# Isengard.net
KiCad netlist of a schematic drawn in Altium Designer
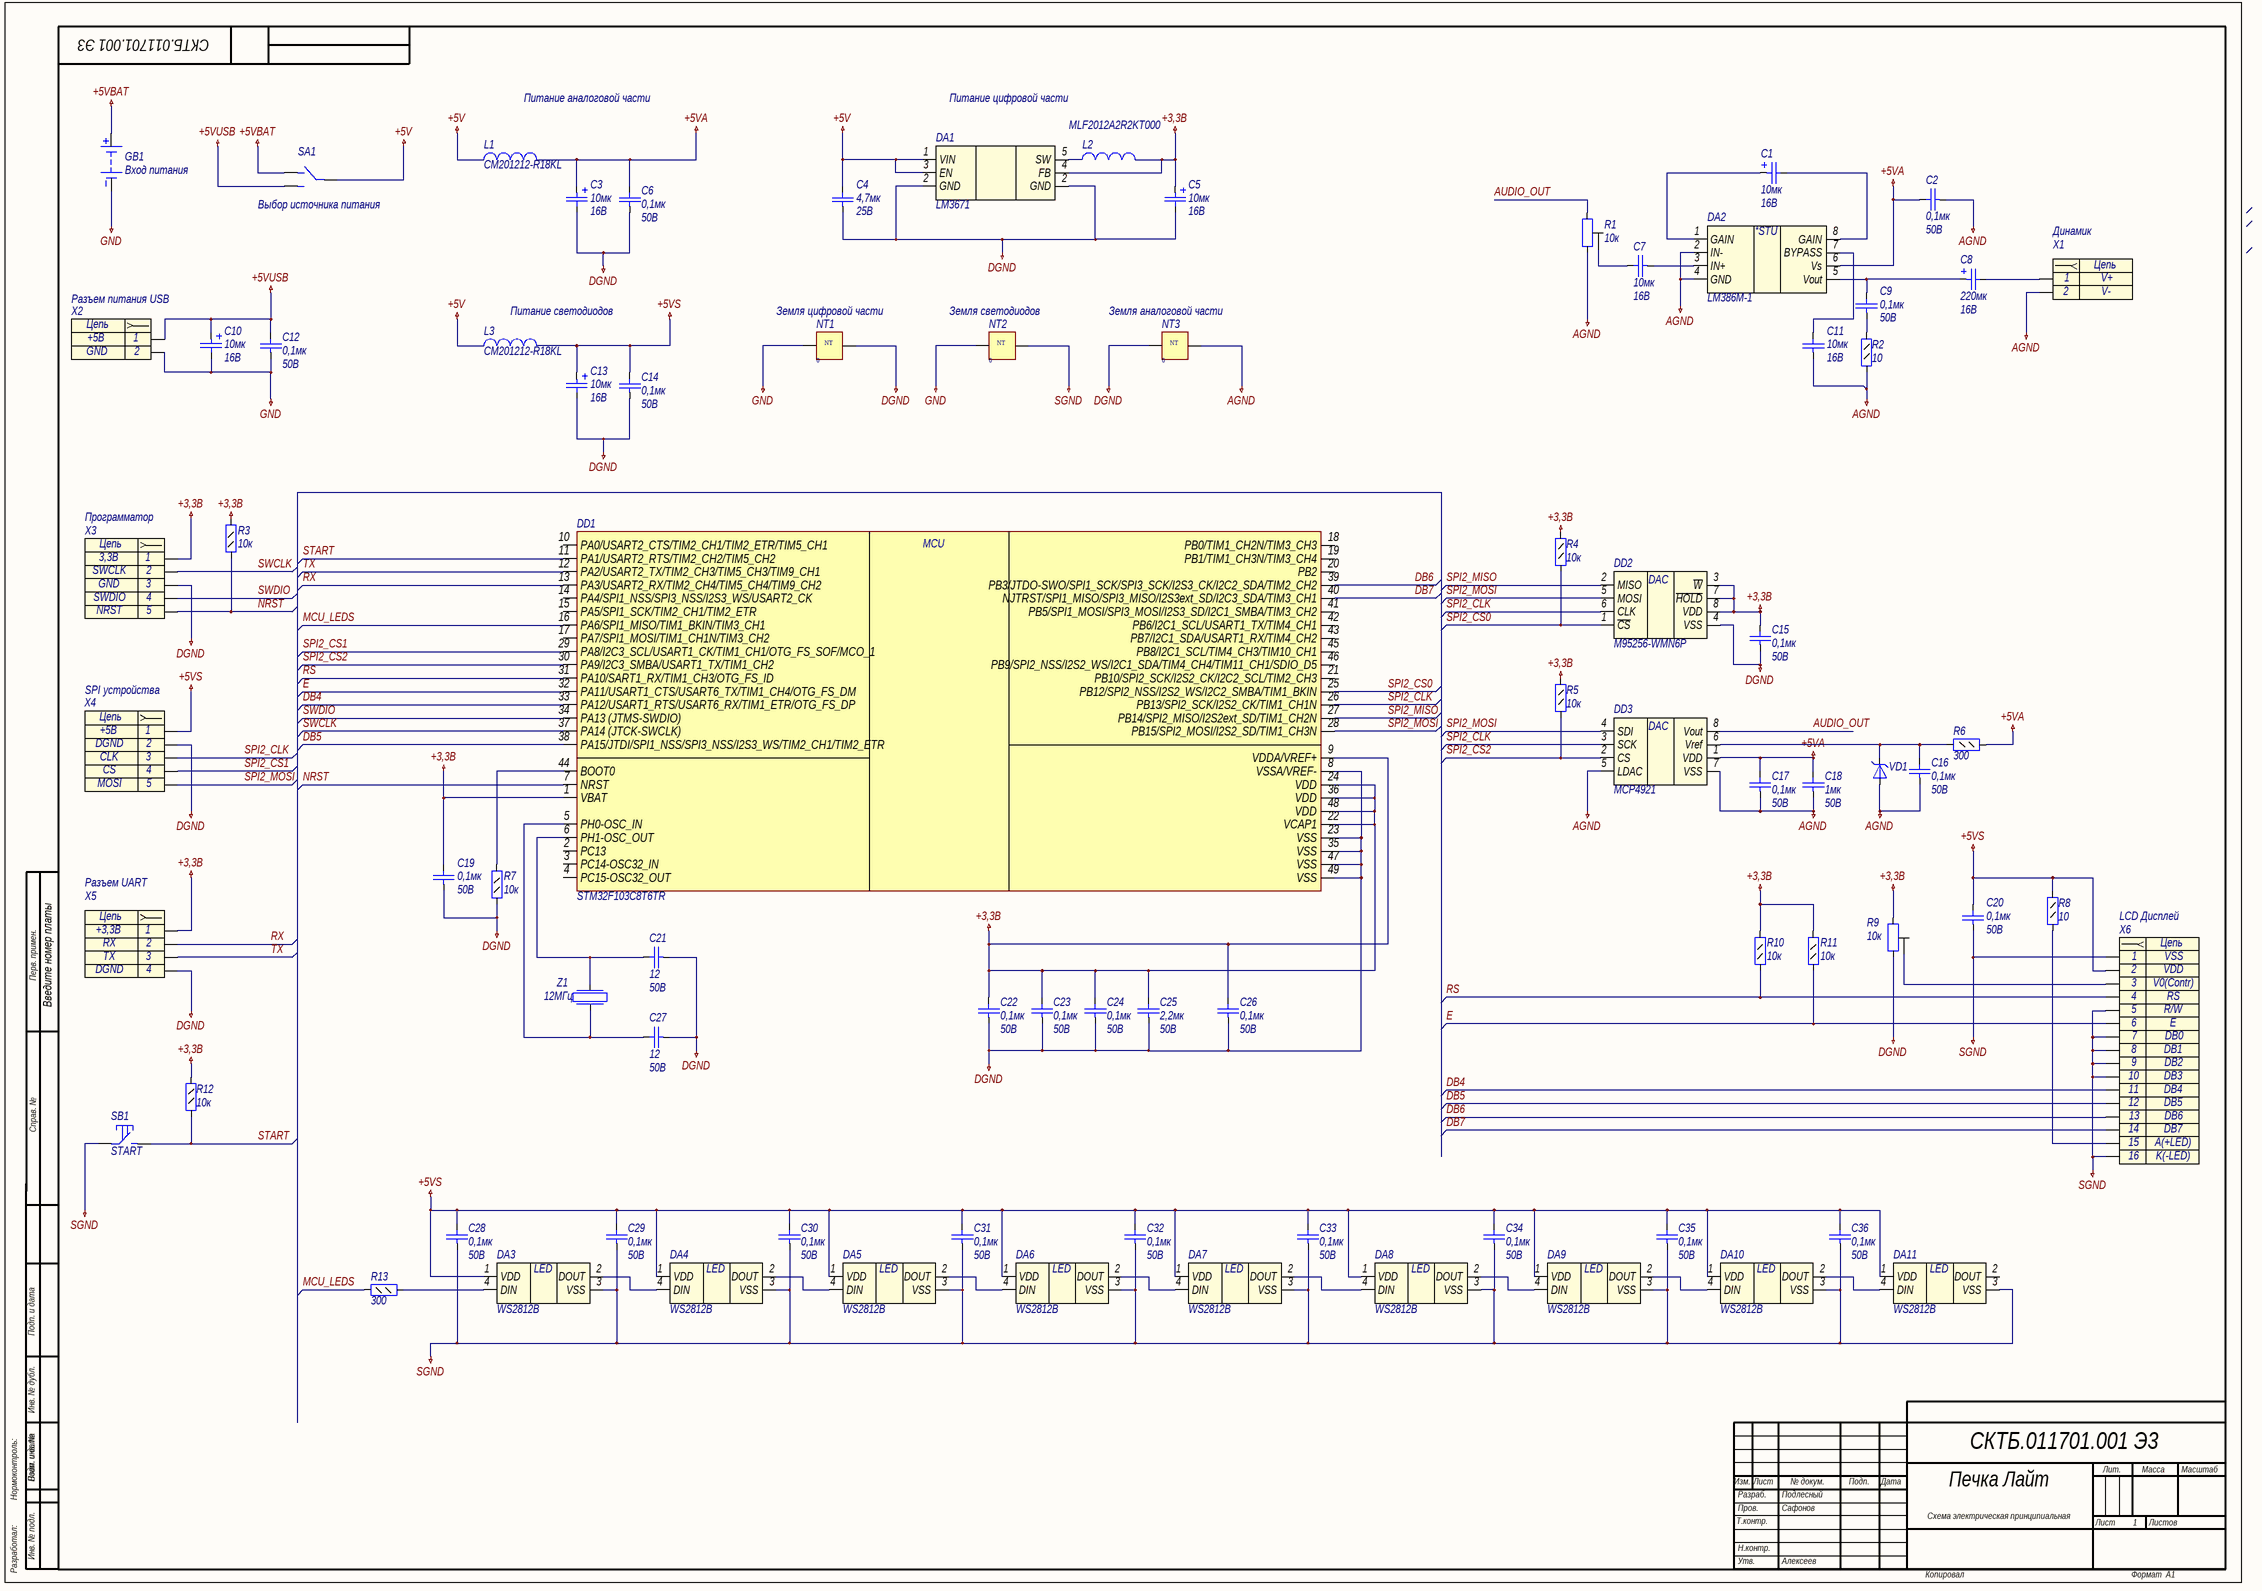
[diagram p0: Isengard.SchDoc]

(export (version "E")
  (design (tool "Eeschema 10.0.6"))
  (components
    (comp (ref "C1")
      (value "10мк")
      (footprint "ZabugorLib:TANTAL CASE B")
      (description "Конденсатор полярный")
      (fields (field (name "VOLTAGE") "16В"))
      (libsource (lib "Isengard") (part "Capacitor_pol"))
    )
    (comp (ref "C2")
      (value "0,1мк")
      (footprint "Isengard:C0805")
      (description "Конденсатор")
      (fields (field (name "VOLTAGE") "50В"))
      (libsource (lib "Isengard") (part "Capacitor"))
    )
    (comp (ref "C3")
      (value "10мк")
      (footprint "ZabugorLib:TANTAL CASE B")
      (description "Конденсатор полярный")
      (fields (field (name "VOLTAGE") "16В"))
      (libsource (lib "Isengard") (part "Capacitor_pol"))
    )
    (comp (ref "C4")
      (value "4,7мк")
      (footprint "ZabugorLib:C0805")
      (description "Конденсатор")
      (fields (field (name "VOLTAGE") "25В"))
      (libsource (lib "Isengard") (part "Capacitor"))
    )
    (comp (ref "C5")
      (value "10мк")
      (footprint "ZabugorLib:TANTAL CASE B")
      (description "Конденсатор полярный")
      (fields (field (name "VOLTAGE") "16В"))
      (libsource (lib "Isengard") (part "Capacitor_pol"))
    )
    (comp (ref "C6")
      (value "0,1мк")
      (footprint "ZabugorLib:C0805")
      (description "Конденсатор")
      (fields (field (name "VOLTAGE") "50В"))
      (libsource (lib "Isengard") (part "Capacitor"))
    )
    (comp (ref "C7")
      (value "10мк")
      (footprint "Isengard:C0805")
      (description "Конденсатор")
      (fields (field (name "VOLTAGE") "16В"))
      (libsource (lib "Isengard") (part "Capacitor"))
    )
    (comp (ref "C8")
      (value "220мк")
      (footprint "Isengard:TANTAL CASE D")
      (description "Конденсатор полярный")
      (fields (field (name "VOLTAGE") "16В"))
      (libsource (lib "Isengard") (part "Capacitor_pol"))
    )
    (comp (ref "C9")
      (value "0,1мк")
      (footprint "Isengard:C0805")
      (description "Конденсатор")
      (fields (field (name "VOLTAGE") "50В"))
      (libsource (lib "Isengard") (part "Capacitor"))
    )
    (comp (ref "C10")
      (value "10мк")
      (footprint "ZabugorLib:TANTAL CASE B")
      (description "Конденсатор полярный")
      (fields (field (name "VOLTAGE") "16В"))
      (libsource (lib "Isengard") (part "Capacitor_pol"))
    )
    (comp (ref "C11")
      (value "10мк")
      (footprint "Isengard:C0805")
      (description "Конденсатор")
      (fields (field (name "VOLTAGE") "16В"))
      (libsource (lib "Isengard") (part "Capacitor"))
    )
    (comp (ref "C12")
      (value "0,1мк")
      (footprint "ZabugorLib:C0805")
      (description "Конденсатор")
      (fields (field (name "VOLTAGE") "50В"))
      (libsource (lib "Isengard") (part "Capacitor"))
    )
    (comp (ref "C13")
      (value "10мк")
      (footprint "ZabugorLib:TANTAL CASE B")
      (description "Конденсатор полярный")
      (fields (field (name "VOLTAGE") "16В"))
      (libsource (lib "Isengard") (part "Capacitor_pol"))
    )
    (comp (ref "C14")
      (value "0,1мк")
      (footprint "ZabugorLib:C0805")
      (description "Конденсатор")
      (fields (field (name "VOLTAGE") "50В"))
      (libsource (lib "Isengard") (part "Capacitor"))
    )
    (comp (ref "C15")
      (value "0,1мк")
      (footprint "ZabugorLib:C0805")
      (description "Конденсатор")
      (fields (field (name "VOLTAGE") "50В"))
      (libsource (lib "Isengard") (part "Capacitor"))
    )
    (comp (ref "C16")
      (value "0,1мк")
      (footprint "ZabugorLib:C0805")
      (description "Конденсатор")
      (fields (field (name "VOLTAGE") "50В"))
      (libsource (lib "Isengard") (part "Capacitor"))
    )
    (comp (ref "C17")
      (value "0,1мк")
      (footprint "ZabugorLib:C0805")
      (description "Конденсатор")
      (fields (field (name "VOLTAGE") "50В"))
      (libsource (lib "Isengard") (part "Capacitor"))
    )
    (comp (ref "C18")
      (value "1мк")
      (footprint "ZabugorLib:C0805")
      (description "Конденсатор")
      (fields (field (name "VOLTAGE") "50В"))
      (libsource (lib "Isengard") (part "Capacitor"))
    )
    (comp (ref "C19")
      (value "0,1мк")
      (footprint "ZabugorLib:C0805")
      (description "Конденсатор")
      (fields (field (name "VOLTAGE") "50В"))
      (libsource (lib "Isengard") (part "Capacitor"))
    )
    (comp (ref "C20")
      (value "0,1мк")
      (footprint "Isengard:C0805")
      (description "Конденсатор")
      (fields (field (name "VOLTAGE") "50В"))
      (libsource (lib "Isengard") (part "Capacitor"))
    )
    (comp (ref "C21")
      (value "12")
      (footprint "ZabugorLib:C0805")
      (description "Конденсатор")
      (fields (field (name "VOLTAGE") "50В"))
      (libsource (lib "Isengard") (part "Capacitor"))
    )
    (comp (ref "C22")
      (value "0,1мк")
      (footprint "ZabugorLib:C0805")
      (description "Конденсатор")
      (fields (field (name "VOLTAGE") "50В"))
      (libsource (lib "Isengard") (part "Capacitor"))
    )
    (comp (ref "C23")
      (value "0,1мк")
      (footprint "ZabugorLib:C0805")
      (description "Конденсатор")
      (fields (field (name "VOLTAGE") "50В"))
      (libsource (lib "Isengard") (part "Capacitor"))
    )
    (comp (ref "C24")
      (value "0,1мк")
      (footprint "ZabugorLib:C0805")
      (description "Конденсатор")
      (fields (field (name "VOLTAGE") "50В"))
      (libsource (lib "Isengard") (part "Capacitor"))
    )
    (comp (ref "C25")
      (value "2,2мк")
      (footprint "ZabugorLib:C0805")
      (description "Конденсатор")
      (fields (field (name "VOLTAGE") "50В"))
      (libsource (lib "Isengard") (part "Capacitor"))
    )
    (comp (ref "C26")
      (value "0,1мк")
      (footprint "ZabugorLib:C0805")
      (description "Конденсатор")
      (fields (field (name "VOLTAGE") "50В"))
      (libsource (lib "Isengard") (part "Capacitor"))
    )
    (comp (ref "C27")
      (value "12")
      (footprint "ZabugorLib:C0805")
      (description "Конденсатор")
      (fields (field (name "VOLTAGE") "50В"))
      (libsource (lib "Isengard") (part "Capacitor"))
    )
    (comp (ref "C28")
      (value "0,1мк")
      (footprint "ZabugorLib:C0805")
      (description "Конденсатор")
      (fields (field (name "VOLTAGE") "50В"))
      (libsource (lib "Isengard") (part "Capacitor"))
    )
    (comp (ref "C29")
      (value "0,1мк")
      (footprint "ZabugorLib:C0805")
      (description "Конденсатор")
      (fields (field (name "VOLTAGE") "50В"))
      (libsource (lib "Isengard") (part "Capacitor"))
    )
    (comp (ref "C30")
      (value "0,1мк")
      (footprint "ZabugorLib:C0805")
      (description "Конденсатор")
      (fields (field (name "VOLTAGE") "50В"))
      (libsource (lib "Isengard") (part "Capacitor"))
    )
    (comp (ref "C31")
      (value "0,1мк")
      (footprint "ZabugorLib:C0805")
      (description "Конденсатор")
      (fields (field (name "VOLTAGE") "50В"))
      (libsource (lib "Isengard") (part "Capacitor"))
    )
    (comp (ref "C32")
      (value "0,1мк")
      (footprint "ZabugorLib:C0805")
      (description "Конденсатор")
      (fields (field (name "VOLTAGE") "50В"))
      (libsource (lib "Isengard") (part "Capacitor"))
    )
    (comp (ref "C33")
      (value "0,1мк")
      (footprint "ZabugorLib:C0805")
      (description "Конденсатор")
      (fields (field (name "VOLTAGE") "50В"))
      (libsource (lib "Isengard") (part "Capacitor"))
    )
    (comp (ref "C34")
      (value "0,1мк")
      (footprint "ZabugorLib:C0805")
      (description "Конденсатор")
      (fields (field (name "VOLTAGE") "50В"))
      (libsource (lib "Isengard") (part "Capacitor"))
    )
    (comp (ref "C35")
      (value "0,1мк")
      (footprint "ZabugorLib:C0805")
      (description "Конденсатор")
      (fields (field (name "VOLTAGE") "50В"))
      (libsource (lib "Isengard") (part "Capacitor"))
    )
    (comp (ref "C36")
      (value "0,1мк")
      (footprint "ZabugorLib:C0805")
      (description "Конденсатор")
      (fields (field (name "VOLTAGE") "50В"))
      (libsource (lib "Isengard") (part "Capacitor"))
    )
    (comp (ref "DA1")
      (value "LM3671")
      (footprint "ZabugorLib:SOT23-5")
      (description "600-mA Step-Down DC-DC Converter")
      (libsource (lib "ZabugorLib") (part "LM3671"))
    )
    (comp (ref "DA2")
      (value "LM386M-1")
      (footprint "ZabugorLib:SO8")
      (description "Low Voltage Audio Power Amplifier")
      (libsource (lib "Isengard") (part "LM386M-1"))
    )
    (comp (ref "DA3")
      (value "WS2812B")
      (footprint "Isengard:WS2812B")
      (description "Светодиод SMD RGB с пиксельной адресацией")
      (fields (field (name "NAME") "WS2812B"))
      (libsource (lib "Isengard") (part "WS2812B"))
    )
    (comp (ref "DA4")
      (value "WS2812B")
      (footprint "Isengard:WS2812B")
      (description "Светодиод SMD RGB с пиксельной адресацией")
      (fields (field (name "NAME") "WS2812B"))
      (libsource (lib "Isengard") (part "WS2812B"))
    )
    (comp (ref "DA5")
      (value "WS2812B")
      (footprint "Isengard:WS2812B")
      (description "Светодиод SMD RGB с пиксельной адресацией")
      (fields (field (name "NAME") "WS2812B"))
      (libsource (lib "Isengard") (part "WS2812B"))
    )
    (comp (ref "DA6")
      (value "WS2812B")
      (footprint "Isengard:WS2812B")
      (description "Светодиод SMD RGB с пиксельной адресацией")
      (fields (field (name "NAME") "WS2812B"))
      (libsource (lib "Isengard") (part "WS2812B"))
    )
    (comp (ref "DA7")
      (value "WS2812B")
      (footprint "Isengard:WS2812B")
      (description "Светодиод SMD RGB с пиксельной адресацией")
      (fields (field (name "NAME") "WS2812B"))
      (libsource (lib "Isengard") (part "WS2812B"))
    )
    (comp (ref "DA8")
      (value "WS2812B")
      (footprint "Isengard:WS2812B")
      (description "Светодиод SMD RGB с пиксельной адресацией")
      (fields (field (name "NAME") "WS2812B"))
      (libsource (lib "Isengard") (part "WS2812B"))
    )
    (comp (ref "DA9")
      (value "WS2812B")
      (footprint "Isengard:WS2812B")
      (description "Светодиод SMD RGB с пиксельной адресацией")
      (fields (field (name "NAME") "WS2812B"))
      (libsource (lib "Isengard") (part "WS2812B"))
    )
    (comp (ref "DA10")
      (value "WS2812B")
      (footprint "Isengard:WS2812B")
      (description "Светодиод SMD RGB с пиксельной адресацией")
      (fields (field (name "NAME") "WS2812B"))
      (libsource (lib "Isengard") (part "WS2812B"))
    )
    (comp (ref "DA11")
      (value "WS2812B")
      (footprint "Isengard:WS2812B")
      (description "Светодиод SMD RGB с пиксельной адресацией")
      (fields (field (name "NAME") "WS2812B"))
      (libsource (lib "Isengard") (part "WS2812B"))
    )
    (comp (ref "DD1")
      (value "STM32F103C8T6TR")
      (footprint "ZabugorLib:LQFP48")
      (libsource (lib "ZabugorLib") (part "STM32F103C8T6TR"))
    )
    (comp (ref "DD2")
      (value "M95256-WMN6P")
      (footprint "ZabugorLib:SO8")
      (description "12-Bit DAC with SPI™ Interface")
      (libsource (lib "ZabugorLib") (part "M95256"))
    )
    (comp (ref "DD3")
      (value "MCP4921")
      (footprint "ZabugorLib:SO8")
      (description "12-Bit DAC with SPI™ Interface")
      (libsource (lib "ZabugorLib") (part "MCP4921"))
    )
    (comp (ref "GB1")
      (value "Вход питания")
      (footprint "Isengard:KLS5-818-С")
      (libsource (lib "Isengard") (part "Battery compartment"))
    )
    (comp (ref "L1")
      (value "CM201212-R18KL")
      (footprint "ZabugorLib:L0805")
      (description "Катушка индуктивности")
      (libsource (lib "Isengard") (part "Inductor"))
    )
    (comp (ref "L2")
      (value "MLF2012A2R2KT000")
      (footprint "ZabugorLib:L0805")
      (description "Катушка индуктивности")
      (libsource (lib "Isengard") (part "Inductor"))
    )
    (comp (ref "L3")
      (value "CM201212-R18KL")
      (footprint "ZabugorLib:L0805")
      (description "Катушка индуктивности")
      (libsource (lib "Isengard") (part "Inductor"))
    )
    (comp (ref "NT1")
      (value "0")
      (footprint "Pofigistor0603")
      (fields (field (name "Comment") "Pofigistor"))
      (libsource (lib "MOP44") (part "Pofigistor"))
    )
    (comp (ref "NT2")
      (value "0")
      (footprint "Pofigistor0603")
      (fields (field (name "Comment") "Pofigistor"))
      (libsource (lib "MOP44") (part "Pofigistor"))
    )
    (comp (ref "NT3")
      (value "0")
      (footprint "Pofigistor0603")
      (fields (field (name "Comment") "Pofigistor"))
      (libsource (lib "MOP44") (part "Pofigistor"))
    )
    (comp (ref "R1")
      (value "10к")
      (footprint "ZabugorLib:Potentiometer")
      (description "Potentiometer")
      (libsource (lib "ZabugorLib") (part "Potentiometer"))
    )
    (comp (ref "R2")
      (value "10")
      (footprint "Isengard:R0805")
      (description "Резистор")
      (libsource (lib "") (part "Resistor_0,125Вт_2"))
    )
    (comp (ref "R3")
      (value "10к")
      (footprint "ZabugorLib:R0805")
      (description "Резистор")
      (libsource (lib "Isengard") (part "Resistor_0,125Вт"))
    )
    (comp (ref "R4")
      (value "10к")
      (footprint "ZabugorLib:R0805")
      (description "Резистор")
      (libsource (lib "") (part "Resistor_0,125Вт_2"))
    )
    (comp (ref "R5")
      (value "10к")
      (footprint "ZabugorLib:R0805")
      (description "Резистор")
      (libsource (lib "") (part "Resistor_0,125Вт_2"))
    )
    (comp (ref "R6")
      (value "300")
      (footprint "Isengard:R0805")
      (description "Резистор")
      (libsource (lib "") (part "Resistor_0,125Вт_1"))
    )
    (comp (ref "R7")
      (value "10к")
      (footprint "ZabugorLib:R0805")
      (description "Резистор")
      (libsource (lib "Isengard") (part "Resistor_0,125Вт"))
    )
    (comp (ref "R8")
      (value "10")
      (footprint "Isengard:R0805")
      (description "Резистор")
      (libsource (lib "") (part "Resistor_0,125Вт_2"))
    )
    (comp (ref "R9")
      (value "10к")
      (footprint "ZabugorLib:Potentiometer")
      (description "Potentiometer")
      (libsource (lib "ZabugorLib") (part "Potentiometer"))
    )
    (comp (ref "R10")
      (value "10к")
      (footprint "Isengard:R0805")
      (description "Резистор")
      (libsource (lib "Isengard") (part "Resistor_0,125Вт"))
    )
    (comp (ref "R11")
      (value "10к")
      (footprint "Isengard:R0805")
      (description "Резистор")
      (libsource (lib "Isengard") (part "Resistor_0,125Вт"))
    )
    (comp (ref "R12")
      (value "10к")
      (footprint "Isengard:R0805")
      (description "Резистор")
      (libsource (lib "") (part "Resistor_0,125Вт_2"))
    )
    (comp (ref "R13")
      (value "300")
      (footprint "ZabugorLib:R0805")
      (description "Резистор")
      (libsource (lib "") (part "Resistor_0,125Вт_3"))
    )
    (comp (ref "SA1")
      (value "Выбор источника питания")
      (footprint "Isengard:KLS7-SS03")
      (description "переключатель однопозиционный")
      (fields (field (name "NAME") "Выбор источника питания"))
      (libsource (lib "Isengard") (part "Toggle switch"))
    )
    (comp (ref "SB1")
      (value "START")
      (footprint "Isengard:Button_SMD_12х12")
      (description "Кнопка")
      (fields (field (name "NAME") "START"))
      (libsource (lib "Isengard") (part "Button_SMD"))
    )
    (comp (ref "VD1")
      (value "LM4040BIM3-2.5/NOPB")
      (footprint "SOT23-3")
      (description "Прецезионный источник опорного напряжения")
      (libsource (lib "MOP44") (part "LM4040BIM3-2.5/NOPB"))
    )
    (comp (ref "X1")
      (value "Динамик")
      (footprint "Isengard:DYNAMIC")
      (description "Разъем - 2 конт. розетка")
      (libsource (lib "") (part "Header_2_sct_1"))
    )
    (comp (ref "X2")
      (value "Разъем питания USB")
      (footprint "Isengard:USB-B Micro 2pin")
      (description "Разъем - 2 конт. розетка")
      (libsource (lib "Isengard") (part "Header_2_sct"))
    )
    (comp (ref "X3")
      (value "Программатор")
      (footprint "Isengard:PLS-5")
      (description "Разъем - 4 конт. розетка")
      (libsource (lib "ZabugorLib") (part "Header_5_sct"))
    )
    (comp (ref "X4")
      (value "SPI устройства")
      (footprint "Isengard:5HOLE_WIRE")
      (description "Разъем - 4 конт. розетка")
      (libsource (lib "Isengard") (part "Header_5_sct"))
    )
    (comp (ref "X5")
      (value "Разъем UART")
      (footprint "Isengard:PLS-4")
      (description "Разъем - 4 конт. розетка")
      (libsource (lib "Isengard") (part "Header_4_sct"))
    )
    (comp (ref "X6")
      (value "LCD Дисплей")
      (footprint "Isengard:PLS-16R")
      (description "Разъем - 16 конт. розетка")
      (libsource (lib "Isengard") (part "Header_16_sct"))
    )
    (comp (ref "Z1")
      (value "12МГц")
      (footprint "ZabugorLib:HC-49SM")
      (description "Кварцевый резонатор")
      (libsource (lib "Isengard") (part "Crystal"))
    )
  )
  (nets
    (net (code "1") (name "+3,3В") (class "Default")
      (node (ref "C15") (pin "2") (pinfunction "2_2") (pintype "passive"))
      (node (ref "C19") (pin "2") (pinfunction "2_2") (pintype "passive"))
      (node (ref "C22") (pin "2") (pinfunction "2_2") (pintype "passive"))
      (node (ref "C23") (pin "2") (pinfunction "2_2") (pintype "passive"))
      (node (ref "C24") (pin "2") (pinfunction "2_2") (pintype "passive"))
      (node (ref "C25") (pin "2") (pinfunction "2_2") (pintype "passive"))
      (node (ref "C26") (pin "2") (pinfunction "2_2") (pintype "passive"))
      (node (ref "C5") (pin "1") (pinfunction "1_1") (pintype "passive"))
      (node (ref "DA1") (pin "4") (pinfunction "FB_4") (pintype "power_in"))
      (node (ref "DD1") (pin "1") (pinfunction "VBAT_1") (pintype "passive"))
      (node (ref "DD1") (pin "22") (pinfunction "VCAP1_22") (pintype "passive"))
      (node (ref "DD1") (pin "24") (pinfunction "VDD_24") (pintype "passive"))
      (node (ref "DD1") (pin "36") (pinfunction "VDD_36") (pintype "passive"))
      (node (ref "DD1") (pin "48") (pinfunction "VDD_48") (pintype "passive"))
      (node (ref "DD1") (pin "9") (pinfunction "VDDA/VREF+_9") (pintype "passive"))
      (node (ref "DD2") (pin "3") (pinfunction "~{W}_3") (pintype "power_in"))
      (node (ref "DD2") (pin "7") (pinfunction "~{HOLD}_7") (pintype "power_in"))
      (node (ref "DD2") (pin "8") (pinfunction "VDD_8") (pintype "power_in"))
      (node (ref "L2") (pin "2") (pinfunction "2_2") (pintype "passive"))
      (node (ref "R10") (pin "2") (pinfunction "5_2") (pintype "passive"))
      (node (ref "R11") (pin "2") (pinfunction "5_2") (pintype "passive"))
      (node (ref "R12") (pin "1") (pinfunction "1_1") (pintype "passive"))
      (node (ref "R3") (pin "2") (pinfunction "5_2") (pintype "passive"))
      (node (ref "R4") (pin "1") (pinfunction "1_1") (pintype "passive"))
      (node (ref "R5") (pin "1") (pinfunction "1_1") (pintype "passive"))
      (node (ref "R9") (pin "1") (pinfunction "1_1") (pintype "passive"))
      (node (ref "X3") (pin "1") (pinfunction "1_1") (pintype "passive"))
      (node (ref "X5") (pin "1") (pinfunction "1_1") (pintype "passive"))
    )
    (net (code "2") (name "+5V") (class "Default")
      (node (ref "C4") (pin "2") (pinfunction "2_2") (pintype "passive"))
      (node (ref "DA1") (pin "1") (pinfunction "VIN_1") (pintype "power_in"))
      (node (ref "DA1") (pin "3") (pinfunction "EN_3") (pintype "power_in"))
      (node (ref "L1") (pin "1") (pinfunction "1_1") (pintype "passive"))
      (node (ref "L3") (pin "1") (pinfunction "1_1") (pintype "passive"))
      (node (ref "SA1") (pin "2") (pinfunction "2_2") (pintype "passive"))
    )
    (net (code "3") (name "+5VA") (class "Default")
      (node (ref "C17") (pin "2") (pinfunction "2_2") (pintype "passive"))
      (node (ref "C18") (pin "2") (pinfunction "2_2") (pintype "passive"))
      (node (ref "C2") (pin "2") (pinfunction "2_2") (pintype "passive"))
      (node (ref "C3") (pin "1") (pinfunction "1_1") (pintype "passive"))
      (node (ref "C6") (pin "2") (pinfunction "2_2") (pintype "passive"))
      (node (ref "DA2") (pin "6") (pinfunction "Vs_6") (pintype "power_in"))
      (node (ref "DD3") (pin "1") (pinfunction "VDD_1") (pintype "power_in"))
      (node (ref "L1") (pin "2") (pinfunction "2_2") (pintype "passive"))
      (node (ref "R6") (pin "1") (pinfunction "1_1") (pintype "passive"))
    )
    (net (code "4") (name "+5VBAT") (class "Default")
      (node (ref "GB1") (pin "1") (pinfunction "1_1") (pintype "passive"))
      (node (ref "SA1") (pin "1") (pinfunction "1_1") (pintype "passive"))
    )
    (net (code "5") (name "+5VS") (class "Default")
      (node (ref "C13") (pin "1") (pinfunction "1_1") (pintype "passive"))
      (node (ref "C14") (pin "2") (pinfunction "2_2") (pintype "passive"))
      (node (ref "C20") (pin "2") (pinfunction "2_2") (pintype "passive"))
      (node (ref "C28") (pin "2") (pinfunction "2_2") (pintype "passive"))
      (node (ref "C29") (pin "2") (pinfunction "2_2") (pintype "passive"))
      (node (ref "C30") (pin "2") (pinfunction "2_2") (pintype "passive"))
      (node (ref "C31") (pin "2") (pinfunction "2_2") (pintype "passive"))
      (node (ref "C32") (pin "2") (pinfunction "2_2") (pintype "passive"))
      (node (ref "C33") (pin "2") (pinfunction "2_2") (pintype "passive"))
      (node (ref "C34") (pin "2") (pinfunction "2_2") (pintype "passive"))
      (node (ref "C35") (pin "2") (pinfunction "2_2") (pintype "passive"))
      (node (ref "C36") (pin "2") (pinfunction "2_2") (pintype "passive"))
      (node (ref "DA10") (pin "1") (pinfunction "VDD_1") (pintype "power_in"))
      (node (ref "DA11") (pin "1") (pinfunction "VDD_1") (pintype "power_in"))
      (node (ref "DA3") (pin "1") (pinfunction "VDD_1") (pintype "power_in"))
      (node (ref "DA4") (pin "1") (pinfunction "VDD_1") (pintype "power_in"))
      (node (ref "DA5") (pin "1") (pinfunction "VDD_1") (pintype "power_in"))
      (node (ref "DA6") (pin "1") (pinfunction "VDD_1") (pintype "power_in"))
      (node (ref "DA7") (pin "1") (pinfunction "VDD_1") (pintype "power_in"))
      (node (ref "DA8") (pin "1") (pinfunction "VDD_1") (pintype "power_in"))
      (node (ref "DA9") (pin "1") (pinfunction "VDD_1") (pintype "power_in"))
      (node (ref "L3") (pin "2") (pinfunction "2_2") (pintype "passive"))
      (node (ref "R8") (pin "1") (pinfunction "1_1") (pintype "passive"))
      (node (ref "X4") (pin "1") (pinfunction "1_1") (pintype "passive"))
      (node (ref "X6") (pin "2") (pinfunction "2_2") (pintype "passive"))
    )
    (net (code "6") (name "+5VUSB") (class "Default")
      (node (ref "C10") (pin "1") (pinfunction "1_1") (pintype "passive"))
      (node (ref "C12") (pin "2") (pinfunction "2_2") (pintype "passive"))
      (node (ref "SA1") (pin "3") (pinfunction "3_3") (pintype "passive"))
      (node (ref "X2") (pin "1") (pinfunction "1_1") (pintype "passive"))
    )
    (net (code "7") (name "/AUDIO_OUT") (class "Default")
      (node (ref "DD3") (pin "8") (pinfunction "Vout_8") (pintype "power_in"))
      (node (ref "R1") (pin "1") (pinfunction "1_1") (pintype "passive"))
    )
    (net (code "8") (name "/DB4") (class "Default")
      (node (ref "DD1") (pin "33") (pinfunction "PA12/USART1_RTS/USART6_RX/TIM1_ETR/OTG_FS_DP_33") (pintype "passive"))
      (node (ref "X6") (pin "11") (pinfunction "11_11") (pintype "passive"))
    )
    (net (code "9") (name "/DB5") (class "Default")
      (node (ref "DD1") (pin "38") (pinfunction "PA15/JTDI/SPI1_NSS/SPI3_NSS/I2S3_WS/TIM2_CH1/TIM2_ETR_38") (pintype "passive"))
      (node (ref "X6") (pin "12") (pinfunction "12_12") (pintype "passive"))
    )
    (net (code "10") (name "/DB6") (class "Default")
      (node (ref "DD1") (pin "39") (pinfunction "PB3/JTDO-SWO/SPI1_SCK/SPI3_SCK/I2S3_CK/I2C2_SDA/TIM2_CH2_39") (pintype "passive"))
      (node (ref "X6") (pin "13") (pinfunction "13_13") (pintype "passive"))
    )
    (net (code "11") (name "/DB7") (class "Default")
      (node (ref "DD1") (pin "40") (pinfunction "NJTRST/SPI1_MISO/SPI3_MISO/I2S3ext_SD/I2C3_SDA/TIM3_CH1_40") (pintype "passive"))
      (node (ref "X6") (pin "14") (pinfunction "14_14") (pintype "passive"))
    )
    (net (code "12") (name "/E") (class "Default")
      (node (ref "DD1") (pin "32") (pinfunction "PA11/USART1_CTS/USART6_TX/TIM1_CH4/OTG_FS_DM_32") (pintype "passive"))
      (node (ref "R11") (pin "1") (pinfunction "1_1") (pintype "passive"))
      (node (ref "X6") (pin "6") (pinfunction "6_6") (pintype "passive"))
    )
    (net (code "13") (name "/MCU_LEDS") (class "Default")
      (node (ref "DD1") (pin "16") (pinfunction "PA6/SPI1_MISO/TIM1_BKIN/TIM3_CH1_16") (pintype "passive"))
      (node (ref "R13") (pin "1") (pinfunction "1_1") (pintype "passive"))
    )
    (net (code "14") (name "/NRST") (class "Default")
      (node (ref "DD1") (pin "7") (pinfunction "NRST_7") (pintype "passive"))
      (node (ref "R3") (pin "1") (pinfunction "1_1") (pintype "passive"))
      (node (ref "X3") (pin "5") (pinfunction "5_5") (pintype "passive"))
    )
    (net (code "15") (name "/RS") (class "Default")
      (node (ref "DD1") (pin "31") (pinfunction "PA10/SART1_RX/TIM1_CH3/OTG_FS_ID_31") (pintype "passive"))
      (node (ref "R10") (pin "1") (pinfunction "1_1") (pintype "passive"))
      (node (ref "X6") (pin "4") (pinfunction "4_4") (pintype "passive"))
    )
    (net (code "16") (name "/RX") (class "Default")
      (node (ref "DD1") (pin "13") (pinfunction "PA3/USART2_RX/TIM2_CH4/TIM5_CH4/TIM9_CH2_13") (pintype "passive"))
      (node (ref "X5") (pin "2") (pinfunction "2_2") (pintype "passive"))
    )
    (net (code "17") (name "/SPI2_CLK") (class "Default")
      (node (ref "DD1") (pin "26") (pinfunction "PB13/SPI2_SCK/I2S2_CK/TIM1_CH1N_26") (pintype "passive"))
      (node (ref "DD2") (pin "6") (pinfunction "CLK_6") (pintype "power_in"))
      (node (ref "DD3") (pin "3") (pinfunction "SCK_3") (pintype "power_in"))
      (node (ref "X4") (pin "3") (pinfunction "3_3") (pintype "passive"))
    )
    (net (code "18") (name "/SPI2_CS0") (class "Default")
      (node (ref "DD1") (pin "25") (pinfunction "PB12/SPI2_NSS/I2S2_WS/I2C2_SMBA/TIM1_BKIN_25") (pintype "passive"))
      (node (ref "DD2") (pin "1") (pinfunction "~{CS}_1") (pintype "power_in"))
      (node (ref "R4") (pin "2") (pinfunction "5_2") (pintype "passive"))
    )
    (net (code "19") (name "/SPI2_CS1") (class "Default")
      (node (ref "DD1") (pin "29") (pinfunction "PA8/I2C3_SCL/USART1_CK/TIM1_CH1/OTG_FS_SOF/MCO_1_29") (pintype "passive"))
      (node (ref "X4") (pin "4") (pinfunction "4_4") (pintype "passive"))
    )
    (net (code "20") (name "/SPI2_CS2") (class "Default")
      (node (ref "DD1") (pin "30") (pinfunction "PA9/I2C3_SMBA/USART1_TX/TIM1_CH2_30") (pintype "passive"))
      (node (ref "DD3") (pin "2") (pinfunction "CS_2") (pintype "power_in"))
      (node (ref "R5") (pin "2") (pinfunction "5_2") (pintype "passive"))
    )
    (net (code "21") (name "/SPI2_MISO") (class "Default")
      (node (ref "DD1") (pin "27") (pinfunction "PB14/SPI2_MISO/I2S2ext_SD/TIM1_CH2N_27") (pintype "passive"))
      (node (ref "DD2") (pin "2") (pinfunction "MISO_2") (pintype "power_in"))
    )
    (net (code "22") (name "/SPI2_MOSI") (class "Default")
      (node (ref "DD1") (pin "28") (pinfunction "PB15/SPI2_MOSI/I2S2_SD/TIM1_CH3N_28") (pintype "passive"))
      (node (ref "DD2") (pin "5") (pinfunction "MOSI_5") (pintype "power_in"))
      (node (ref "DD3") (pin "4") (pinfunction "SDI_4") (pintype "power_in"))
      (node (ref "X4") (pin "5") (pinfunction "5_5") (pintype "passive"))
    )
    (net (code "23") (name "/START") (class "Default")
      (node (ref "DD1") (pin "11") (pinfunction "PA1/USART2_RTS/TIM2_CH2/TIM5_CH2_11") (pintype "passive"))
      (node (ref "R12") (pin "2") (pinfunction "5_2") (pintype "passive"))
      (node (ref "SB1") (pin "4") (pinfunction "4_4") (pintype "passive"))
    )
    (net (code "24") (name "/SWCLK") (class "Default")
      (node (ref "DD1") (pin "37") (pinfunction "PA14_(JTCK-SWCLK)_37") (pintype "passive"))
      (node (ref "X3") (pin "2") (pinfunction "2_2") (pintype "passive"))
    )
    (net (code "25") (name "/SWDIO") (class "Default")
      (node (ref "DD1") (pin "34") (pinfunction "PA13_(JTMS-SWDIO)_34") (pintype "passive"))
      (node (ref "X3") (pin "4") (pinfunction "4_4") (pintype "passive"))
    )
    (net (code "26") (name "/TX") (class "Default")
      (node (ref "DD1") (pin "12") (pinfunction "PA2/USART2_TX/TIM2_CH3/TIM5_CH3/TIM9_CH1_12") (pintype "passive"))
      (node (ref "X5") (pin "3") (pinfunction "3_3") (pintype "passive"))
    )
    (net (code "27") (name "AGND") (class "Default")
      (node (ref "C11") (pin "1") (pinfunction "1_1") (pintype "passive"))
      (node (ref "C16") (pin "1") (pinfunction "1_1") (pintype "passive"))
      (node (ref "C17") (pin "1") (pinfunction "1_1") (pintype "passive"))
      (node (ref "C18") (pin "1") (pinfunction "1_1") (pintype "passive"))
      (node (ref "C2") (pin "1") (pinfunction "1_1") (pintype "passive"))
      (node (ref "DA2") (pin "2") (pinfunction "IN-_2") (pintype "power_in"))
      (node (ref "DA2") (pin "4") (pinfunction "GND_4") (pintype "power_in"))
      (node (ref "DD3") (pin "5") (pinfunction "LDAC_5") (pintype "power_in"))
      (node (ref "DD3") (pin "7") (pinfunction "VSS_7") (pintype "power_in"))
      (node (ref "NT3") (pin "2") (pinfunction "2_2") (pintype "passive"))
      (node (ref "R1") (pin "3") (pinfunction "3_3") (pintype "passive"))
      (node (ref "R2") (pin "2") (pinfunction "5_2") (pintype "passive"))
      (node (ref "VD1") (pin "2") (pinfunction "A_2") (pintype "passive"))
      (node (ref "X1") (pin "2") (pinfunction "2_2") (pintype "passive"))
    )
    (net (code "28") (name "DGND") (class "Default")
      (node (ref "C13") (pin "2") (pinfunction "2_2") (pintype "passive"))
      (node (ref "C14") (pin "1") (pinfunction "1_1") (pintype "passive"))
      (node (ref "C15") (pin "1") (pinfunction "1_1") (pintype "passive"))
      (node (ref "C19") (pin "1") (pinfunction "1_1") (pintype "passive"))
      (node (ref "C21") (pin "1") (pinfunction "1_1") (pintype "passive"))
      (node (ref "C22") (pin "1") (pinfunction "1_1") (pintype "passive"))
      (node (ref "C23") (pin "1") (pinfunction "1_1") (pintype "passive"))
      (node (ref "C24") (pin "1") (pinfunction "1_1") (pintype "passive"))
      (node (ref "C25") (pin "1") (pinfunction "1_1") (pintype "passive"))
      (node (ref "C26") (pin "1") (pinfunction "1_1") (pintype "passive"))
      (node (ref "C27") (pin "1") (pinfunction "1_1") (pintype "passive"))
      (node (ref "C3") (pin "2") (pinfunction "2_2") (pintype "passive"))
      (node (ref "C4") (pin "1") (pinfunction "1_1") (pintype "passive"))
      (node (ref "C5") (pin "2") (pinfunction "2_2") (pintype "passive"))
      (node (ref "C6") (pin "1") (pinfunction "1_1") (pintype "passive"))
      (node (ref "DA1") (pin "2") (pinfunction "GND_2") (pintype "power_in"))
      (node (ref "DD1") (pin "23") (pinfunction "VSS_23") (pintype "passive"))
      (node (ref "DD1") (pin "35") (pinfunction "VSS_35") (pintype "passive"))
      (node (ref "DD1") (pin "47") (pinfunction "VSS_47") (pintype "passive"))
      (node (ref "DD1") (pin "49") (pinfunction "VSS_49") (pintype "passive"))
      (node (ref "DD1") (pin "8") (pinfunction "VSSA/VREF-_8") (pintype "passive"))
      (node (ref "DD2") (pin "4") (pinfunction "VSS_4") (pintype "power_in"))
      (node (ref "NT1") (pin "2") (pinfunction "2_2") (pintype "passive"))
      (node (ref "NT3") (pin "1") (pinfunction "1_1") (pintype "passive"))
      (node (ref "R7") (pin "1") (pinfunction "1_1") (pintype "passive"))
      (node (ref "R9") (pin "3") (pinfunction "3_3") (pintype "passive"))
      (node (ref "X3") (pin "3") (pinfunction "3_3") (pintype "passive"))
      (node (ref "X4") (pin "2") (pinfunction "2_2") (pintype "passive"))
      (node (ref "X5") (pin "4") (pinfunction "4_4") (pintype "passive"))
    )
    (net (code "29") (name "GND") (class "Default")
      (node (ref "C10") (pin "2") (pinfunction "2_2") (pintype "passive"))
      (node (ref "C12") (pin "1") (pinfunction "1_1") (pintype "passive"))
      (node (ref "GB1") (pin "2") (pinfunction "2_2") (pintype "passive"))
      (node (ref "NT1") (pin "1") (pinfunction "1_1") (pintype "passive"))
      (node (ref "NT2") (pin "1") (pinfunction "1_1") (pintype "passive"))
      (node (ref "X2") (pin "2") (pinfunction "2_2") (pintype "passive"))
    )
    (net (code "30") (name "Net-(C1-Pad1)") (class "Default")
      (node (ref "C1") (pin "1") (pinfunction "1_1") (pintype "passive"))
      (node (ref "DA2") (pin "1") (pinfunction "GAIN_1") (pintype "power_in"))
    )
    (net (code "31") (name "Net-(C1-Pad2)") (class "Default")
      (node (ref "C1") (pin "2") (pinfunction "2_2") (pintype "passive"))
      (node (ref "DA2") (pin "8") (pinfunction "GAIN_8") (pintype "power_in"))
    )
    (net (code "32") (name "Net-(C7-Pad2)") (class "Default")
      (node (ref "C7") (pin "2") (pinfunction "2_2") (pintype "passive"))
      (node (ref "R1") (pin "2") (pinfunction "2_2") (pintype "passive"))
    )
    (net (code "33") (name "Net-(C8-Pad2)") (class "Default")
      (node (ref "C8") (pin "2") (pinfunction "2_2") (pintype "passive"))
      (node (ref "X1") (pin "1") (pinfunction "1_1") (pintype "passive"))
    )
    (net (code "34") (name "Net-(C9-Pad1)") (class "Default")
      (node (ref "C9") (pin "1") (pinfunction "1_1") (pintype "passive"))
      (node (ref "R2") (pin "1") (pinfunction "1_1") (pintype "passive"))
    )
    (net (code "35") (name "Net-(DA1-SW)") (class "Default")
      (node (ref "DA1") (pin "5") (pinfunction "SW_5") (pintype "power_in"))
      (node (ref "L2") (pin "1") (pinfunction "1_1") (pintype "passive"))
    )
    (net (code "36") (name "Net-(DA2-BYPASS)") (class "Default")
      (node (ref "C11") (pin "2") (pinfunction "2_2") (pintype "passive"))
      (node (ref "DA2") (pin "7") (pinfunction "BYPASS_7") (pintype "power_in"))
    )
    (net (code "37") (name "Net-(DA2-IN+)") (class "Default")
      (node (ref "C7") (pin "1") (pinfunction "1_1") (pintype "passive"))
      (node (ref "DA2") (pin "3") (pinfunction "IN+_3") (pintype "power_in"))
    )
    (net (code "38") (name "Net-(DA2-Vout)") (class "Default")
      (node (ref "C8") (pin "1") (pinfunction "1_1") (pintype "passive"))
      (node (ref "C9") (pin "2") (pinfunction "2_2") (pintype "passive"))
      (node (ref "DA2") (pin "5") (pinfunction "Vout_5") (pintype "power_in"))
    )
    (net (code "39") (name "Net-(DA3-DIN)") (class "Default")
      (node (ref "DA3") (pin "4") (pinfunction "DIN_4") (pintype "power_in"))
      (node (ref "R13") (pin "2") (pinfunction "5_2") (pintype "passive"))
    )
    (net (code "40") (name "Net-(DA3-DOUT)") (class "Default")
      (node (ref "DA3") (pin "2") (pinfunction "DOUT_2") (pintype "power_in"))
      (node (ref "DA4") (pin "4") (pinfunction "DIN_4") (pintype "power_in"))
    )
    (net (code "41") (name "Net-(DA4-DOUT)") (class "Default")
      (node (ref "DA4") (pin "2") (pinfunction "DOUT_2") (pintype "power_in"))
      (node (ref "DA5") (pin "4") (pinfunction "DIN_4") (pintype "power_in"))
    )
    (net (code "42") (name "Net-(DA5-DOUT)") (class "Default")
      (node (ref "DA5") (pin "2") (pinfunction "DOUT_2") (pintype "power_in"))
      (node (ref "DA6") (pin "4") (pinfunction "DIN_4") (pintype "power_in"))
    )
    (net (code "43") (name "Net-(DA6-DOUT)") (class "Default")
      (node (ref "DA6") (pin "2") (pinfunction "DOUT_2") (pintype "power_in"))
      (node (ref "DA7") (pin "4") (pinfunction "DIN_4") (pintype "power_in"))
    )
    (net (code "44") (name "Net-(DA7-DOUT)") (class "Default")
      (node (ref "DA7") (pin "2") (pinfunction "DOUT_2") (pintype "power_in"))
      (node (ref "DA8") (pin "4") (pinfunction "DIN_4") (pintype "power_in"))
    )
    (net (code "45") (name "Net-(DA8-DOUT)") (class "Default")
      (node (ref "DA8") (pin "2") (pinfunction "DOUT_2") (pintype "power_in"))
      (node (ref "DA9") (pin "4") (pinfunction "DIN_4") (pintype "power_in"))
    )
    (net (code "46") (name "Net-(DA10-DIN)") (class "Default")
      (node (ref "DA10") (pin "4") (pinfunction "DIN_4") (pintype "power_in"))
      (node (ref "DA9") (pin "2") (pinfunction "DOUT_2") (pintype "power_in"))
    )
    (net (code "47") (name "Net-(DA10-DOUT)") (class "Default")
      (node (ref "DA10") (pin "2") (pinfunction "DOUT_2") (pintype "power_in"))
      (node (ref "DA11") (pin "4") (pinfunction "DIN_4") (pintype "power_in"))
    )
    (net (code "48") (name "Net-(DD1-BOOT0)") (class "Default")
      (node (ref "DD1") (pin "44") (pinfunction "BOOT0_44") (pintype "passive"))
      (node (ref "R7") (pin "2") (pinfunction "5_2") (pintype "passive"))
    )
    (net (code "49") (name "Net-(DD1-PH0-OSC_IN)") (class "Default")
      (node (ref "C27") (pin "2") (pinfunction "2_2") (pintype "passive"))
      (node (ref "DD1") (pin "5") (pinfunction "PH0-OSC_IN_5") (pintype "passive"))
      (node (ref "Z1") (pin "1") (pinfunction "1_1") (pintype "passive"))
    )
    (net (code "50") (name "Net-(DD1-PH1-OSC_OUT)") (class "Default")
      (node (ref "C21") (pin "2") (pinfunction "2_2") (pintype "passive"))
      (node (ref "DD1") (pin "6") (pinfunction "PH1-OSC_OUT_6") (pintype "passive"))
      (node (ref "Z1") (pin "2") (pinfunction "2_2") (pintype "passive"))
    )
    (net (code "51") (name "Net-(DD3-Vref)") (class "Default")
      (node (ref "C16") (pin "2") (pinfunction "2_2") (pintype "passive"))
      (node (ref "DD3") (pin "6") (pinfunction "Vref_6") (pintype "power_in"))
      (node (ref "R6") (pin "2") (pinfunction "5_2") (pintype "passive"))
      (node (ref "VD1") (pin "1") (pinfunction "K_1") (pintype "passive"))
    )
    (net (code "52") (name "Net-(R8-5)") (class "Default")
      (node (ref "R8") (pin "2") (pinfunction "5_2") (pintype "passive"))
      (node (ref "X6") (pin "15") (pinfunction "15_15") (pintype "passive"))
    )
    (net (code "53") (name "Net-(R9-Pad2)") (class "Default")
      (node (ref "R9") (pin "2") (pinfunction "2_2") (pintype "passive"))
      (node (ref "X6") (pin "3") (pinfunction "3_3") (pintype "passive"))
    )
    (net (code "54") (name "SGND") (class "Default")
      (node (ref "C20") (pin "1") (pinfunction "1_1") (pintype "passive"))
      (node (ref "C28") (pin "1") (pinfunction "1_1") (pintype "passive"))
      (node (ref "C29") (pin "1") (pinfunction "1_1") (pintype "passive"))
      (node (ref "C30") (pin "1") (pinfunction "1_1") (pintype "passive"))
      (node (ref "C31") (pin "1") (pinfunction "1_1") (pintype "passive"))
      (node (ref "C32") (pin "1") (pinfunction "1_1") (pintype "passive"))
      (node (ref "C33") (pin "1") (pinfunction "1_1") (pintype "passive"))
      (node (ref "C34") (pin "1") (pinfunction "1_1") (pintype "passive"))
      (node (ref "C35") (pin "1") (pinfunction "1_1") (pintype "passive"))
      (node (ref "C36") (pin "1") (pinfunction "1_1") (pintype "passive"))
      (node (ref "DA10") (pin "3") (pinfunction "VSS_3") (pintype "power_in"))
      (node (ref "DA11") (pin "3") (pinfunction "VSS_3") (pintype "power_in"))
      (node (ref "DA3") (pin "3") (pinfunction "VSS_3") (pintype "power_in"))
      (node (ref "DA4") (pin "3") (pinfunction "VSS_3") (pintype "power_in"))
      (node (ref "DA5") (pin "3") (pinfunction "VSS_3") (pintype "power_in"))
      (node (ref "DA6") (pin "3") (pinfunction "VSS_3") (pintype "power_in"))
      (node (ref "DA7") (pin "3") (pinfunction "VSS_3") (pintype "power_in"))
      (node (ref "DA8") (pin "3") (pinfunction "VSS_3") (pintype "power_in"))
      (node (ref "DA9") (pin "3") (pinfunction "VSS_3") (pintype "power_in"))
      (node (ref "NT2") (pin "2") (pinfunction "2_2") (pintype "passive"))
      (node (ref "SB1") (pin "1") (pinfunction "1_1") (pintype "passive"))
      (node (ref "X6") (pin "1") (pinfunction "1_1") (pintype "passive"))
      (node (ref "X6") (pin "10") (pinfunction "10_10") (pintype "passive"))
      (node (ref "X6") (pin "16") (pinfunction "16_16") (pintype "passive"))
      (node (ref "X6") (pin "5") (pinfunction "5_5") (pintype "passive"))
      (node (ref "X6") (pin "7") (pinfunction "7_7") (pintype "passive"))
      (node (ref "X6") (pin "8") (pinfunction "8_8") (pintype "passive"))
      (node (ref "X6") (pin "9") (pinfunction "9_9") (pintype "passive"))
    )
    (net (code "55") (name "unconnected-(DA11-DOUT-Pad2)") (class "Default")
      (node (ref "DA11") (pin "2") (pinfunction "DOUT_2") (pintype "power_in"))
    )
    (net (code "56") (name "unconnected-(DD1-PA0{slash}USART2_CTS{slash}TIM2_CH1{slash}TIM2_ETR{slash}TIM5_CH1-Pad10)") (class "Default")
      (node (ref "DD1") (pin "10") (pinfunction "PA0/USART2_CTS/TIM2_CH1/TIM2_ETR/TIM5_CH1_10") (pintype "passive"))
    )
    (net (code "57") (name "unconnected-(DD1-PA4{slash}SPI1_NSS{slash}SPI3_NSS{slash}I2S3_WS{slash}USART2_CK-Pad14)") (class "Default")
      (node (ref "DD1") (pin "14") (pinfunction "PA4/SPI1_NSS/SPI3_NSS/I2S3_WS/USART2_CK_14") (pintype "passive"))
    )
    (net (code "58") (name "unconnected-(DD1-PA5{slash}SPI1_SCK{slash}TIM2_CH1{slash}TIM2_ETR-Pad15)") (class "Default")
      (node (ref "DD1") (pin "15") (pinfunction "PA5/SPI1_SCK/TIM2_CH1/TIM2_ETR_15") (pintype "passive"))
    )
    (net (code "59") (name "unconnected-(DD1-PA7{slash}SPI1_MOSI{slash}TIM1_CH1N{slash}TIM3_CH2-Pad17)") (class "Default")
      (node (ref "DD1") (pin "17") (pinfunction "PA7/SPI1_MOSI/TIM1_CH1N/TIM3_CH2_17") (pintype "passive"))
    )
    (net (code "60") (name "unconnected-(DD1-PB0{slash}TIM1_CH2N{slash}TIM3_CH3-Pad18)") (class "Default")
      (node (ref "DD1") (pin "18") (pinfunction "PB0/TIM1_CH2N/TIM3_CH3_18") (pintype "passive"))
    )
    (net (code "61") (name "unconnected-(DD1-PB1{slash}TIM1_CH3N{slash}TIM3_CH4-Pad19)") (class "Default")
      (node (ref "DD1") (pin "19") (pinfunction "PB1/TIM1_CH3N/TIM3_CH4_19") (pintype "passive"))
    )
    (net (code "62") (name "unconnected-(DD1-PB2-Pad20)") (class "Default")
      (node (ref "DD1") (pin "20") (pinfunction "PB2_20") (pintype "passive"))
    )
    (net (code "63") (name "unconnected-(DD1-PB5{slash}SPI1_MOSI{slash}SPI3_MOSI{slash}I2S3_SD{slash}I2C1_SMBA{slash}TIM3_CH2-Pad41)") (class "Default")
      (node (ref "DD1") (pin "41") (pinfunction "PB5/SPI1_MOSI/SPI3_MOSI/I2S3_SD/I2C1_SMBA/TIM3_CH2_41") (pintype "passive"))
    )
    (net (code "64") (name "unconnected-(DD1-PB6{slash}I2C1_SCL{slash}USART1_TX{slash}TIM4_CH1-Pad42)") (class "Default")
      (node (ref "DD1") (pin "42") (pinfunction "PB6/I2C1_SCL/USART1_TX/TIM4_CH1_42") (pintype "passive"))
    )
    (net (code "65") (name "unconnected-(DD1-PB7{slash}I2C1_SDA{slash}USART1_RX{slash}TIM4_CH2-Pad43)") (class "Default")
      (node (ref "DD1") (pin "43") (pinfunction "PB7/I2C1_SDA/USART1_RX/TIM4_CH2_43") (pintype "passive"))
    )
    (net (code "66") (name "unconnected-(DD1-PB8{slash}I2C1_SCL{slash}TIM4_CH3{slash}TIM10_CH1-Pad45)") (class "Default")
      (node (ref "DD1") (pin "45") (pinfunction "PB8/I2C1_SCL/TIM4_CH3/TIM10_CH1_45") (pintype "passive"))
    )
    (net (code "67") (name "unconnected-(DD1-PB9{slash}SPI2_NSS{slash}I2S2_WS{slash}I2C1_SDA{slash}TIM4_CH4{slash}TIM11_CH1{slash}SDIO_D5-Pad46)") (class "Default")
      (node (ref "DD1") (pin "46") (pinfunction "PB9/SPI2_NSS/I2S2_WS/I2C1_SDA/TIM4_CH4/TIM11_CH1/SDIO_D5_46") (pintype "passive"))
    )
    (net (code "68") (name "unconnected-(DD1-PB10{slash}SPI2_SCK{slash}I2S2_CK{slash}I2C2_SCL{slash}TIM2_CH3-Pad21)") (class "Default")
      (node (ref "DD1") (pin "21") (pinfunction "PB10/SPI2_SCK/I2S2_CK/I2C2_SCL/TIM2_CH3_21") (pintype "passive"))
    )
    (net (code "69") (name "unconnected-(DD1-PC13-Pad2)") (class "Default")
      (node (ref "DD1") (pin "2") (pinfunction "PC13_2") (pintype "passive"))
    )
    (net (code "70") (name "unconnected-(DD1-PC14-OSC32_IN-Pad3)") (class "Default")
      (node (ref "DD1") (pin "3") (pinfunction "PC14-OSC32_IN_3") (pintype "passive"))
    )
    (net (code "71") (name "unconnected-(DD1-PC15-OSC32_OUT-Pad4)") (class "Default")
      (node (ref "DD1") (pin "4") (pinfunction "PC15-OSC32_OUT_4") (pintype "passive"))
    )
  )
)
